# 02-SENSORS.net
KiCad netlist of a schematic drawn in Altium Designer
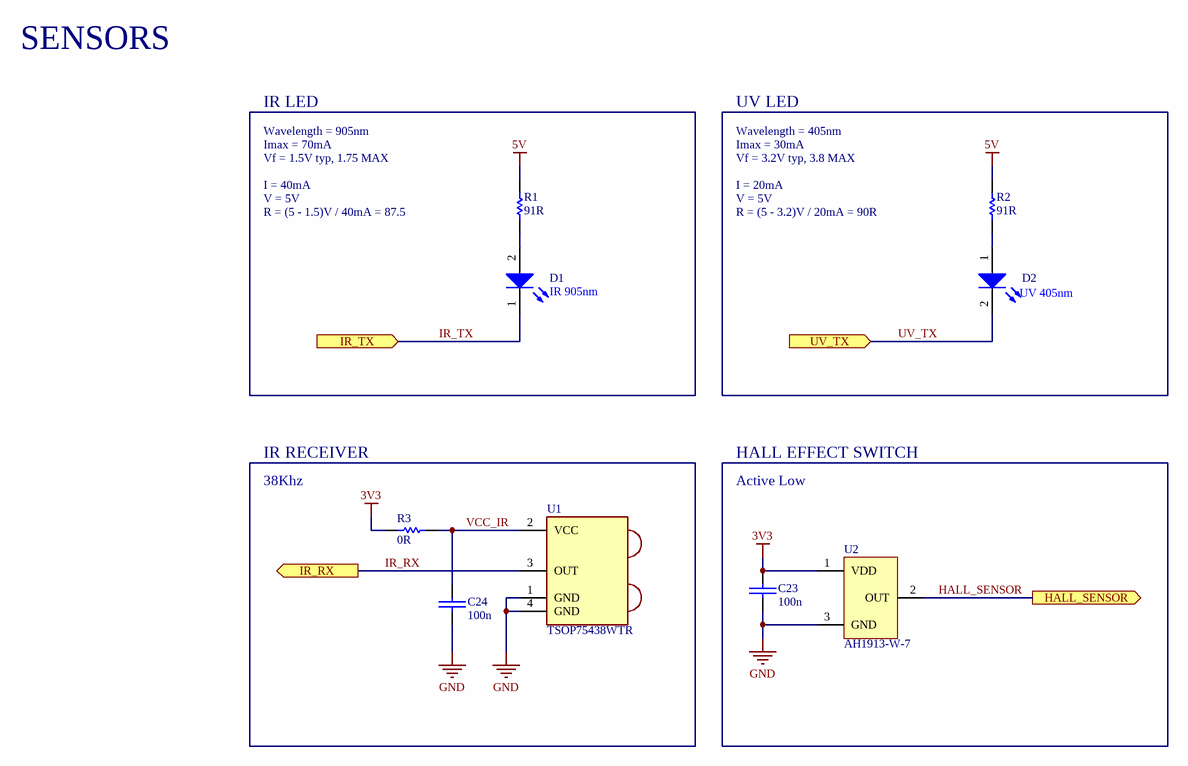
[diagram p0: 02-SENSORS.SchDoc]

(export (version "E")
  (design (tool "Eeschema 10.0.6"))
  (components
    (comp (ref "C23")
      (value "100n")
      (footprint "CAPC100X50X65")
      (description "CAP CER 100nF 25V X5R 0402")
      (fields (field (name "MANUFACTURER") "Murata Electronics"))
      (libsource (lib "FishWand_Schlib") (part "C_100NF_25V_X5R_0402"))
    )
    (comp (ref "C24")
      (value "100n")
      (footprint "CAPC100X50X65")
      (description "CAP CER 100nF 25V X5R 0402")
      (fields (field (name "MANUFACTURER") "Murata Electronics"))
      (libsource (lib "FishWand_Schlib") (part "C_100NF_25V_X5R_0402"))
    )
    (comp (ref "D1")
      (value "IR 905nm")
      (footprint "LED_SFH_4045N")
      (description "Infrared (IR) Emitter 950nm 1.6V 70mA 90mW/sr @ 70mA 18Â° 2-SMD, No Lead")
      (fields
        (field (name "MANUFACTURER") "OSRAM Opto")
        (field (name "DIGI-KEY_PART_NUMBER") "475-3047-1-ND")
      )
      (libsource (lib "FishWand_Schlib") (part "LED_SFH_4045N_IR_950nm"))
    )
    (comp (ref "D2")
      (value "UV 405nm")
      (footprint "LED_VLMU3100-GS08")
      (description "Ultraviolet (UV) Emitter 405nm 3.2V 30mA 2.5mW/sr @ 20mA 120° 2-PLCC")
      (fields
        (field (name "MANUFACTURER") "Vishay Semiconductor Opto Division")
        (field (name "Comment") "LED")
      )
      (libsource (lib "FishWand_Schlib") (part "LED_VLMU3100-GS08_EMITTER_UV_405NM_30MA"))
    )
    (comp (ref "R1")
      (value "91R")
      (footprint "RESC0402")
      (description "91 Ohms ±5% 0.063W, 1/16W Chip Resistor 0402 (1005 Metric) Moisture Resistant Thick Film")
      (fields (field (name "MANUFACTURER") "YAGEO") (field (name "TOLERANCE") "5%"))
      (libsource (lib "FishWand_Schlib") (part "R_0402_90R_5%"))
    )
    (comp (ref "R2")
      (value "91R")
      (footprint "RESC0402")
      (description "91 Ohms ±5% 0.063W, 1/16W Chip Resistor 0402 (1005 Metric) Moisture Resistant Thick Film")
      (fields (field (name "MANUFACTURER") "YAGEO") (field (name "TOLERANCE") "5%"))
      (libsource (lib "FishWand_Schlib") (part "R_0402_90R_5%"))
    )
    (comp (ref "R3")
      (value "0R")
      (footprint "RESC0402")
      (description "0 Ohms Jumper 0.063W, 1/16W Chip Resistor 0402 (1005 Metric) Thick Film")
      (fields (field (name "MANUFACTURER") "YAGEO") (field (name "TOLERANCE") "5%"))
      (libsource (lib "FishWand_Schlib") (part "R_0402_0R_5%"))
    )
    (comp (ref "U1")
      (value "TSOP75438WTR")
      (footprint "TSOP75438WTR")
      (description "Remote Receiver Sensor 38.0kHz 45m Surface Mount")
      (fields (field (name "MANUFACTURER") "Vishay Semiconductor Opto Division"))
      (libsource (lib "FishWand_Schlib") (part "TSOP75438WTR_IR_38Khz_REMOTE"))
    )
    (comp (ref "U2")
      (value "AH1913-W-7")
      (footprint "SC59-3")
      (description "MAG SWITCH OMNIPOL SC59-3 T&R")
      (fields (field (name "MANUFACTURER") "Diodes Incorporated"))
      (libsource (lib "FishWand_Schlib") (part "U_MAG_SWITCH _AH1913-W-7"))
    )
  )
  (nets
    (net (code "1") (name "/HALL_SENSOR") (class "Default")
      (node (ref "U2") (pin "2") (pinfunction "OUT_2") (pintype "passive"))
    )
    (net (code "2") (name "/IR_RX") (class "Default")
      (node (ref "U1") (pin "3") (pinfunction "OUT_3") (pintype "passive"))
    )
    (net (code "3") (name "/IR_TX") (class "Default")
      (node (ref "D1") (pin "1") (pinfunction "1_1") (pintype "passive"))
    )
    (net (code "4") (name "/UV_TX") (class "Default")
      (node (ref "D2") (pin "2") (pinfunction "K_2") (pintype "passive"))
    )
    (net (code "5") (name "/VCC_IR") (class "Default")
      (node (ref "C24") (pin "1") (pinfunction "1_1") (pintype "passive"))
      (node (ref "R3") (pin "2") (pinfunction "2_2") (pintype "passive"))
      (node (ref "U1") (pin "2") (pinfunction "VCC_2") (pintype "passive"))
    )
    (net (code "6") (name "3V3") (class "Default")
      (node (ref "C23") (pin "1") (pinfunction "1_1") (pintype "passive"))
      (node (ref "R3") (pin "1") (pinfunction "1_1") (pintype "passive"))
      (node (ref "U2") (pin "1") (pinfunction "VDD_1") (pintype "passive"))
    )
    (net (code "7") (name "5V") (class "Default")
      (node (ref "R1") (pin "2") (pinfunction "2_2") (pintype "passive"))
      (node (ref "R2") (pin "2") (pinfunction "2_2") (pintype "passive"))
    )
    (net (code "8") (name "GND") (class "Default")
      (node (ref "C23") (pin "2") (pinfunction "2_2") (pintype "passive"))
      (node (ref "C24") (pin "2") (pinfunction "2_2") (pintype "passive"))
      (node (ref "U1") (pin "1") (pinfunction "GND_1") (pintype "passive"))
      (node (ref "U1") (pin "4") (pinfunction "GND_4") (pintype "passive"))
      (node (ref "U2") (pin "3") (pinfunction "GND_3") (pintype "passive"))
    )
    (net (code "9") (name "Net-(D1-Pad2)") (class "Default")
      (node (ref "D1") (pin "2") (pinfunction "2_2") (pintype "passive"))
      (node (ref "R1") (pin "1") (pinfunction "1_1") (pintype "passive"))
    )
    (net (code "10") (name "Net-(D2-A)") (class "Default")
      (node (ref "D2") (pin "1") (pinfunction "A_1") (pintype "passive"))
      (node (ref "R2") (pin "1") (pinfunction "1_1") (pintype "passive"))
    )
  )
)
